# INTERNAL_REGULATORS.net
KiCad netlist of a schematic drawn in Altium Designer
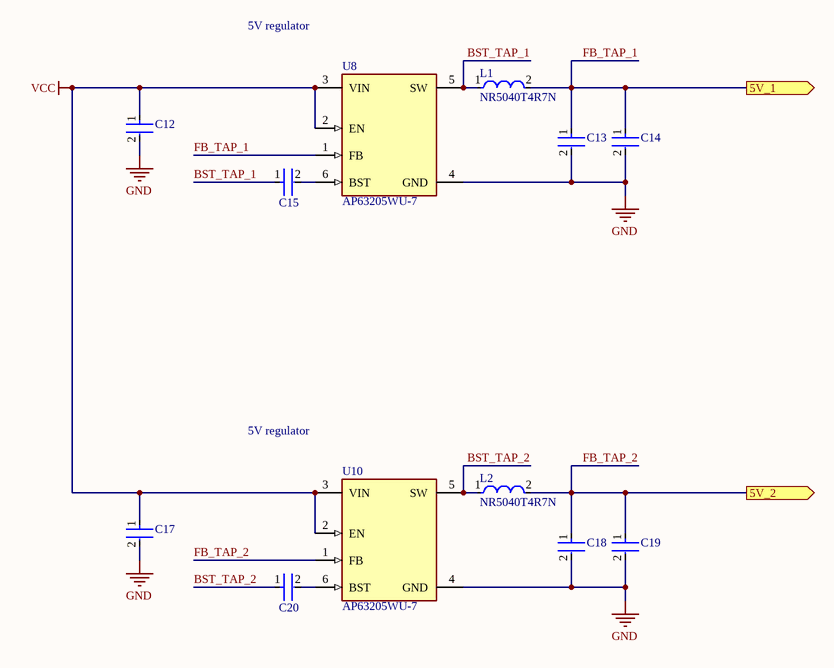
[diagram p0: INTERNAL_REGULATORS.SchDoc]

(export (version "E")
  (design (tool "Eeschema 10.0.6"))
  (components
    (comp (ref "C12")
      (value "C0805C106K8PACTU")
      (footprint "FP-C0805C-DG-MFG")
      (description "CAP CER 10UF 10V X5R 0805")
      (fields (field (name "TOLERANCE") "10%") (field (name "MANUFACTURER") "Kemet"))
      (libsource (lib "Altium Content Vault") (part "11868f565c42a9108669ba33697ecf6"))
    )
    (comp (ref "C13")
      (value "GRM21BR61E226ME44L")
      (footprint "FP-GRM21B-0_2-e0_2_0_7-IPC_B")
      (description "Chip Multilayer Ceramic Capacitors for General Purpose, 0805, 22uF, X5R, 15%, 20%, 25V")
      (fields (field (name "TOLERANCE") "20%") (field (name "VOLTAGE") "25V"))
      (libsource (lib "Altium Content Vault") (part "b4654b650e69147ec39a6b967a45e02"))
    )
    (comp (ref "C14")
      (value "GRM21BR61E226ME44L")
      (footprint "FP-GRM21B-0_2-e0_2_0_7-IPC_B")
      (description "Chip Multilayer Ceramic Capacitors for General Purpose, 0805, 22uF, X5R, 15%, 20%, 25V")
      (fields (field (name "TOLERANCE") "20%") (field (name "VOLTAGE") "25V"))
      (libsource (lib "Altium Content Vault") (part "b4654b650e69147ec39a6b967a45e02"))
    )
    (comp (ref "C15")
      (value "C0402C104K8PACTU")
      (footprint "FP-C0402-BB-MFG")
      (description "CAP CER 0.1UF 10V X5R 0402")
      (fields (field (name "MANUFACTURER") "Kemet") (field (name "TOLERANCE") "0.1"))
      (libsource (lib "Altium Content Vault") (part "b4654b650e69147ec39a6b967a45e02"))
    )
    (comp (ref "C17")
      (value "C0805C106K8PACTU")
      (footprint "FP-C0805C-DG-MFG")
      (description "CAP CER 10UF 10V X5R 0805")
      (fields (field (name "TOLERANCE") "10%") (field (name "MANUFACTURER") "Kemet"))
      (libsource (lib "Altium Content Vault") (part "11868f565c42a9108669ba33697ecf6"))
    )
    (comp (ref "C18")
      (value "GRM21BR61E226ME44L")
      (footprint "FP-GRM21B-0_2-e0_2_0_7-IPC_B")
      (description "Chip Multilayer Ceramic Capacitors for General Purpose, 0805, 22uF, X5R, 15%, 20%, 25V")
      (fields (field (name "TOLERANCE") "20%") (field (name "VOLTAGE") "25V"))
      (libsource (lib "Altium Content Vault") (part "b4654b650e69147ec39a6b967a45e02"))
    )
    (comp (ref "C19")
      (value "GRM21BR61E226ME44L")
      (footprint "FP-GRM21B-0_2-e0_2_0_7-IPC_B")
      (description "Chip Multilayer Ceramic Capacitors for General Purpose, 0805, 22uF, X5R, 15%, 20%, 25V")
      (fields (field (name "TOLERANCE") "20%") (field (name "VOLTAGE") "25V"))
      (libsource (lib "Altium Content Vault") (part "b4654b650e69147ec39a6b967a45e02"))
    )
    (comp (ref "C20")
      (value "C0402C104K8PACTU")
      (footprint "FP-C0402-BB-MFG")
      (description "CAP CER 0.1UF 10V X5R 0402")
      (fields (field (name "MANUFACTURER") "Kemet") (field (name "TOLERANCE") "0.1"))
      (libsource (lib "Altium Content Vault") (part "b4654b650e69147ec39a6b967a45e02"))
    )
    (comp (ref "L1")
      (value "NR5040T4R7N")
      (footprint "FP-NR5040-H_4_1-MFG")
      (description "SMD Power Inductors 4.7uH ±30% 3.1A 37.7mΩ")
      (fields (field (name "TOLERANCE") "30%"))
      (libsource (lib "Altium Content Vault") (part "725321dda6339637d4d059423bc1c3c"))
    )
    (comp (ref "L2")
      (value "NR5040T4R7N")
      (footprint "FP-NR5040-H_4_1-MFG")
      (description "SMD Power Inductors 4.7uH ±30% 3.1A 37.7mΩ")
      (fields (field (name "TOLERANCE") "30%"))
      (libsource (lib "Altium Content Vault") (part "725321dda6339637d4d059423bc1c3c"))
    )
    (comp (ref "U8")
      (value "AP63205WU-7")
      (footprint "FP-TSOT26-MFG")
      (description "IC REG BUCK 5V 2A TSOT26")
      (fields
        (field (name "MANUFACTURER") "Diodes Inc.")
        (field (name "OCTOPART") "https://octopart.com/ap63205wu-7-diodes+inc.-98099551")
      )
      (libsource (lib "Altium Content Vault") (part "029bc9fbfa4a99dbb8b3a24c2adb655"))
    )
    (comp (ref "U10")
      (value "AP63205WU-7")
      (footprint "FP-TSOT26-MFG")
      (description "IC REG BUCK 5V 2A TSOT26")
      (fields
        (field (name "MANUFACTURER") "Diodes Inc.")
        (field (name "OCTOPART") "https://octopart.com/ap63205wu-7-diodes+inc.-98099551")
      )
      (libsource (lib "Altium Content Vault") (part "029bc9fbfa4a99dbb8b3a24c2adb655"))
    )
  )
  (nets
    (net (code "1") (name "/BST_TAP_1") (class "Default")
      (node (ref "C15") (pin "1") (pinfunction "1_1") (pintype "passive"))
      (node (ref "L1") (pin "1") (pinfunction "1_1") (pintype "passive"))
      (node (ref "U8") (pin "5") (pinfunction "SW_5") (pintype "power_in"))
    )
    (net (code "2") (name "/BST_TAP_2") (class "Default")
      (node (ref "C20") (pin "1") (pinfunction "1_1") (pintype "passive"))
      (node (ref "L2") (pin "1") (pinfunction "1_1") (pintype "passive"))
      (node (ref "U10") (pin "5") (pinfunction "SW_5") (pintype "power_in"))
    )
    (net (code "3") (name "/FB_TAP_1") (class "Default")
      (node (ref "C13") (pin "1") (pinfunction "1_1") (pintype "passive"))
      (node (ref "C14") (pin "1") (pinfunction "1_1") (pintype "passive"))
      (node (ref "L1") (pin "2") (pinfunction "2_2") (pintype "passive"))
      (node (ref "U8") (pin "1") (pinfunction "FB_1") (pintype "input"))
    )
    (net (code "4") (name "/FB_TAP_2") (class "Default")
      (node (ref "C18") (pin "1") (pinfunction "1_1") (pintype "passive"))
      (node (ref "C19") (pin "1") (pinfunction "1_1") (pintype "passive"))
      (node (ref "L2") (pin "2") (pinfunction "2_2") (pintype "passive"))
      (node (ref "U10") (pin "1") (pinfunction "FB_1") (pintype "input"))
    )
    (net (code "5") (name "GND") (class "Default")
      (node (ref "C12") (pin "2") (pinfunction "2_2") (pintype "passive"))
      (node (ref "C13") (pin "2") (pinfunction "2_2") (pintype "passive"))
      (node (ref "C14") (pin "2") (pinfunction "2_2") (pintype "passive"))
      (node (ref "C17") (pin "2") (pinfunction "2_2") (pintype "passive"))
      (node (ref "C18") (pin "2") (pinfunction "2_2") (pintype "passive"))
      (node (ref "C19") (pin "2") (pinfunction "2_2") (pintype "passive"))
      (node (ref "U10") (pin "4") (pinfunction "GND_4") (pintype "power_in"))
      (node (ref "U8") (pin "4") (pinfunction "GND_4") (pintype "power_in"))
    )
    (net (code "6") (name "Net-(U8-BST)") (class "Default")
      (node (ref "C15") (pin "2") (pinfunction "2_2") (pintype "passive"))
      (node (ref "U8") (pin "6") (pinfunction "BST_6") (pintype "input"))
    )
    (net (code "7") (name "Net-(U10-BST)") (class "Default")
      (node (ref "C20") (pin "2") (pinfunction "2_2") (pintype "passive"))
      (node (ref "U10") (pin "6") (pinfunction "BST_6") (pintype "input"))
    )
    (net (code "8") (name "VCC") (class "Default")
      (node (ref "C12") (pin "1") (pinfunction "1_1") (pintype "passive"))
      (node (ref "C17") (pin "1") (pinfunction "1_1") (pintype "passive"))
      (node (ref "U10") (pin "2") (pinfunction "EN_2") (pintype "input"))
      (node (ref "U10") (pin "3") (pinfunction "VIN_3") (pintype "power_in"))
      (node (ref "U8") (pin "2") (pinfunction "EN_2") (pintype "input"))
      (node (ref "U8") (pin "3") (pinfunction "VIN_3") (pintype "power_in"))
    )
  )
)
